# SoC_PS.net
KiCad netlist of a schematic drawn in Altium Designer
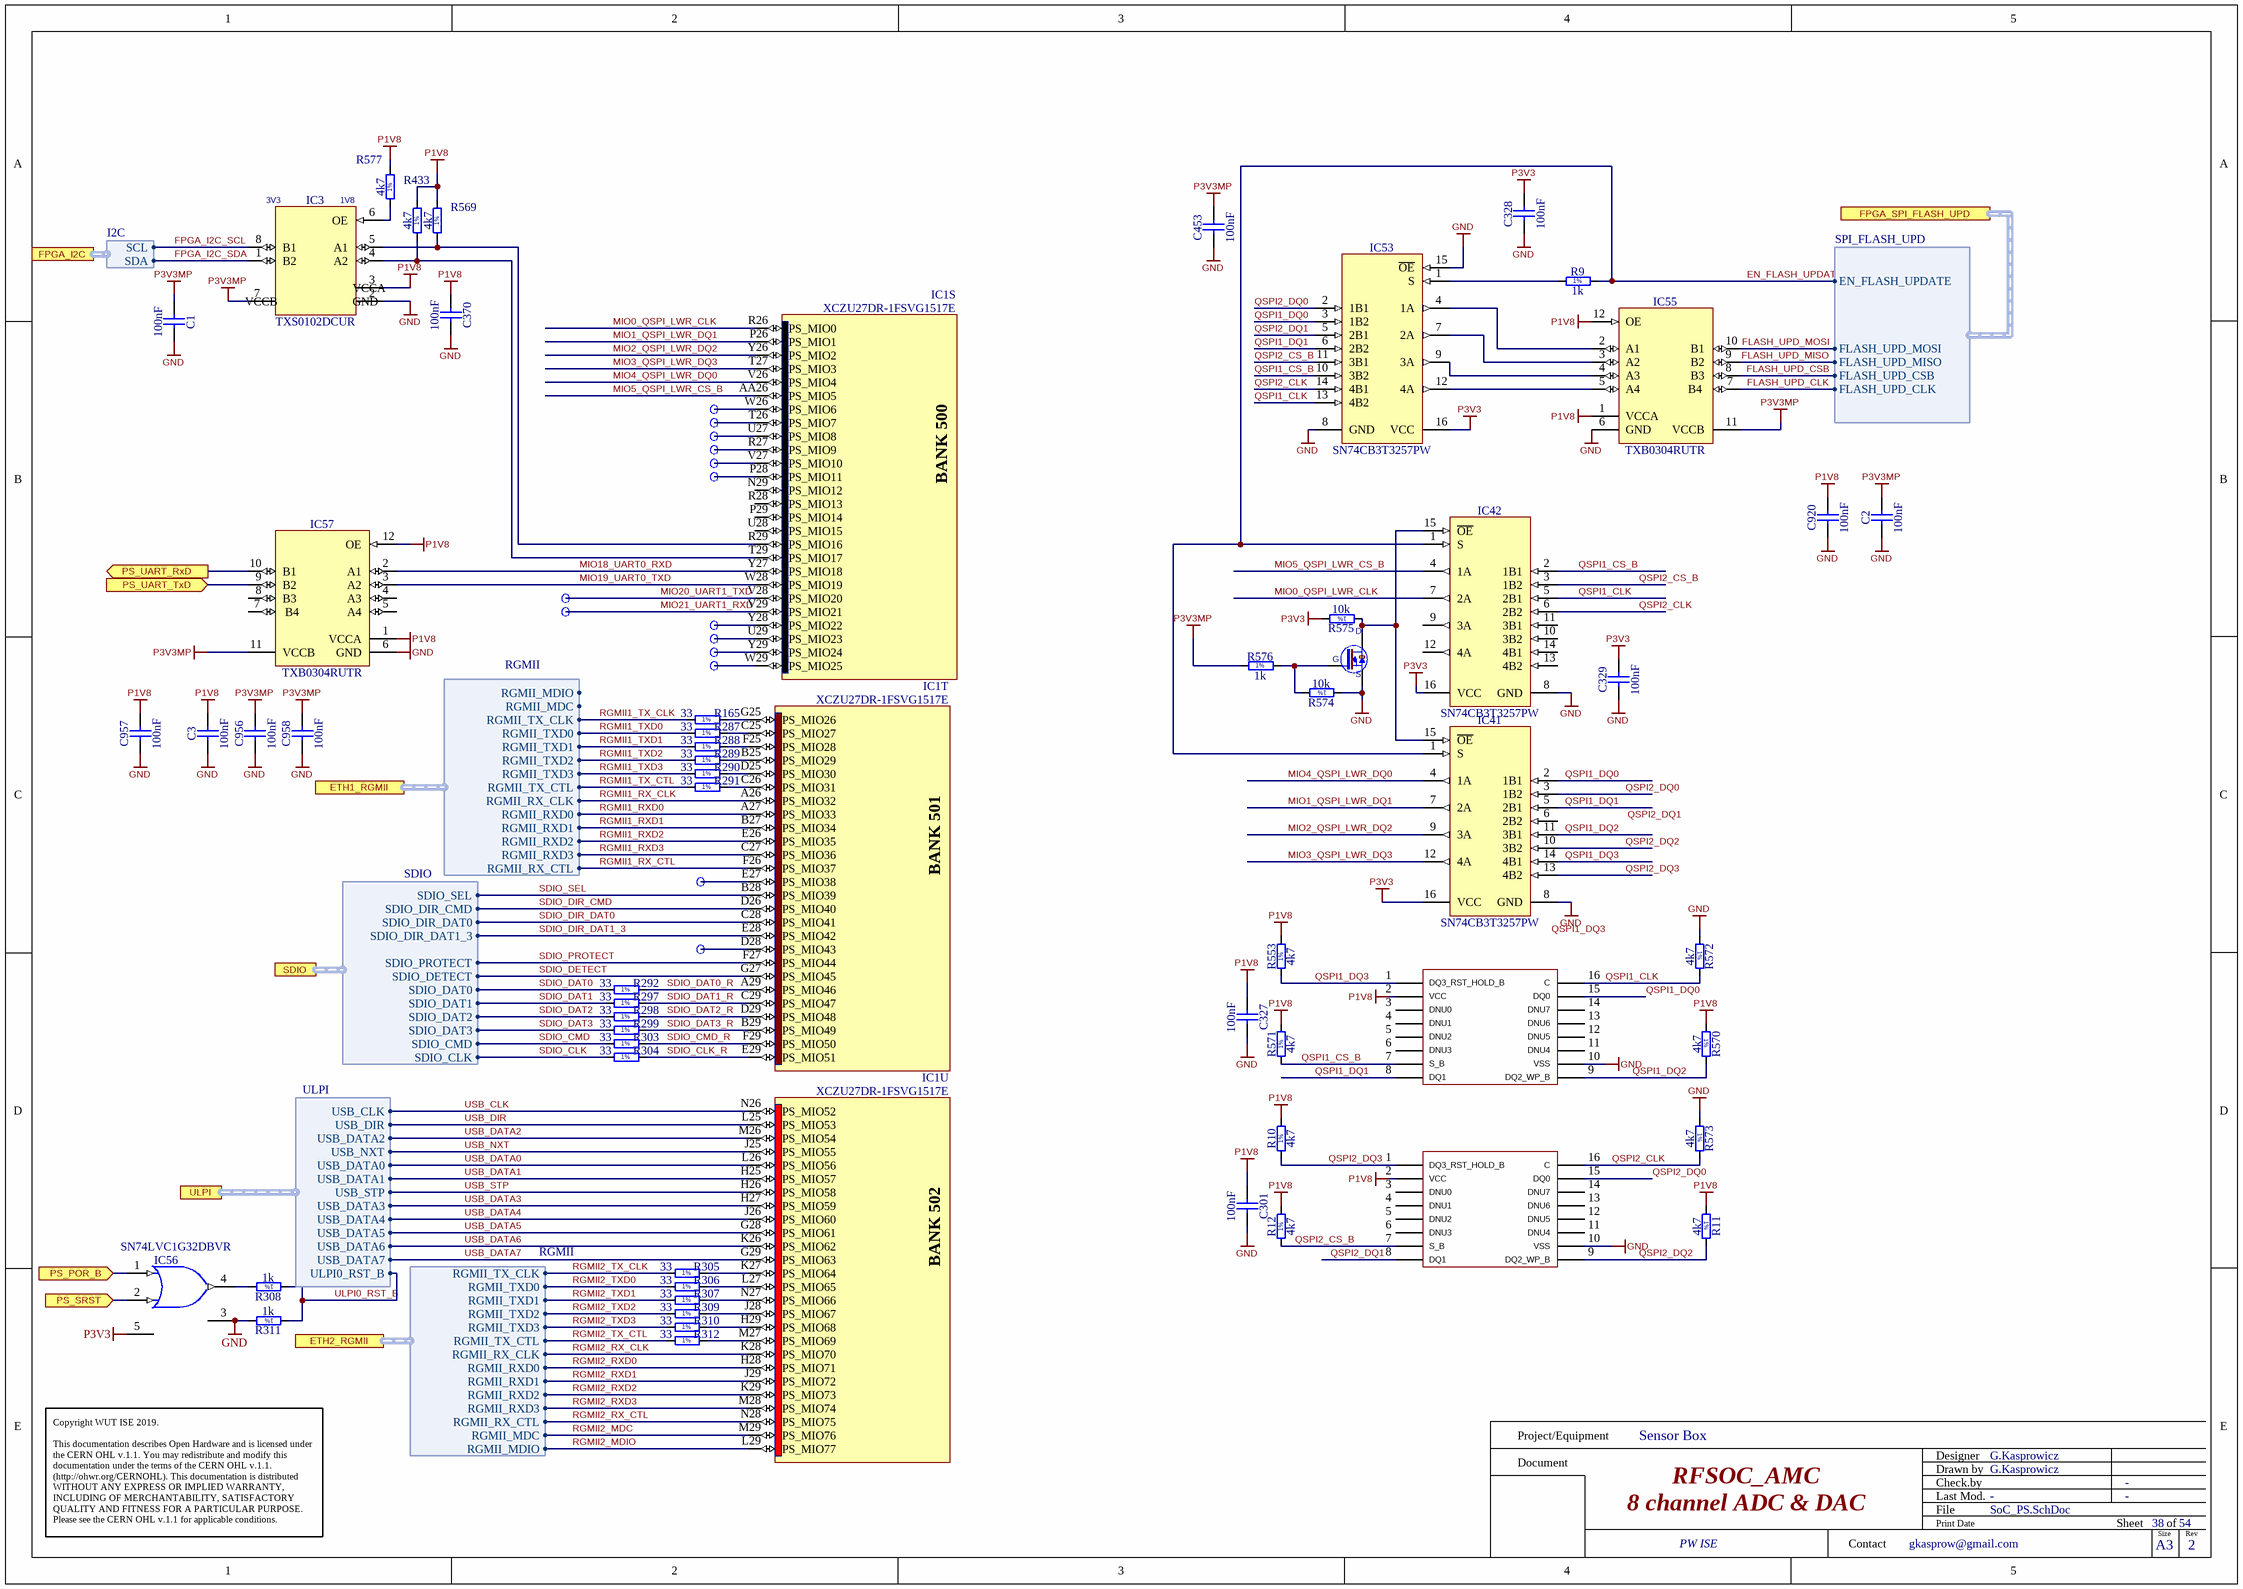
[diagram p0: SoC_PS.SchDoc]

(export (version "E")
  (design (tool "Eeschema 10.0.6"))
  (components
    (comp (ref "C1")
      (value "100nF")
      (footprint "CAPC0603X33N")
      (description "Non-polarised capacitor")
      (fields
        (field (name "MANUFACTURER PART NUMBER") "CC0201_100NF_6.3V_10%_X5R")
        (field (name "MANUFACTURER") "GENERIC")
        (field (name "AUTHOR") "CERN DEM JLC")
      )
      (libsource (lib "Capacitors") (part "Capacitor - non polarized"))
    )
    (comp (ref "C2")
      (value "100nF")
      (footprint "CAPC0603X33N")
      (description "Non-polarised capacitor")
      (fields
        (field (name "MANUFACTURER PART NUMBER") "CC0201_100NF_6.3V_10%_X5R")
        (field (name "MANUFACTURER") "GENERIC")
        (field (name "AUTHOR") "CERN DEM JLC")
      )
      (libsource (lib "Capacitors") (part "Capacitor - non polarized"))
    )
    (comp (ref "C3")
      (value "100nF")
      (footprint "CAPC0603X33N")
      (description "Non-polarised capacitor")
      (fields
        (field (name "MANUFACTURER PART NUMBER") "CC0201_100NF_6.3V_10%_X5R")
        (field (name "MANUFACTURER") "GENERIC")
        (field (name "AUTHOR") "CERN DEM JLC")
      )
      (libsource (lib "Capacitors") (part "Capacitor - non polarized"))
    )
    (comp (ref "C301")
      (value "100nF")
      (footprint "CAPC0603X33N")
      (description "Non-polarised capacitor")
      (fields
        (field (name "MANUFACTURER PART NUMBER") "CC0201_100NF_6.3V_10%_X5R")
        (field (name "MANUFACTURER") "GENERIC")
        (field (name "AUTHOR") "CERN DEM JLC")
      )
      (libsource (lib "Capacitors") (part "Capacitor - non polarized"))
    )
    (comp (ref "C327")
      (value "100nF")
      (footprint "CAPC0603X33N")
      (description "Non-polarised capacitor")
      (fields
        (field (name "MANUFACTURER PART NUMBER") "CC0201_100NF_6.3V_10%_X5R")
        (field (name "MANUFACTURER") "GENERIC")
        (field (name "AUTHOR") "CERN DEM JLC")
      )
      (libsource (lib "Capacitors") (part "Capacitor - non polarized"))
    )
    (comp (ref "C328")
      (value "100nF")
      (footprint "CAPC0603X33N")
      (description "Non-polarised capacitor")
      (fields
        (field (name "MANUFACTURER PART NUMBER") "CC0201_100NF_6.3V_10%_X5R")
        (field (name "MANUFACTURER") "GENERIC")
        (field (name "AUTHOR") "CERN DEM JLC")
      )
      (libsource (lib "Capacitors") (part "Capacitor - non polarized"))
    )
    (comp (ref "C329")
      (value "100nF")
      (footprint "CAPC0603X33N")
      (description "Non-polarised capacitor")
      (fields
        (field (name "MANUFACTURER PART NUMBER") "CC0201_100NF_6.3V_10%_X5R")
        (field (name "MANUFACTURER") "GENERIC")
        (field (name "AUTHOR") "CERN DEM JLC")
      )
      (libsource (lib "Capacitors") (part "Capacitor - non polarized"))
    )
    (comp (ref "C370")
      (value "100nF")
      (footprint "CAPC0603X33N")
      (description "Non-polarised capacitor")
      (fields
        (field (name "MANUFACTURER PART NUMBER") "CC0201_100NF_6.3V_10%_X5R")
        (field (name "MANUFACTURER") "GENERIC")
        (field (name "AUTHOR") "CERN DEM JLC")
      )
      (libsource (lib "Capacitors") (part "Capacitor - non polarized"))
    )
    (comp (ref "C453")
      (value "100nF")
      (footprint "CAPC0603X33N")
      (description "Non-polarised capacitor")
      (fields
        (field (name "MANUFACTURER PART NUMBER") "CC0201_100NF_6.3V_10%_X5R")
        (field (name "MANUFACTURER") "GENERIC")
        (field (name "AUTHOR") "CERN DEM JLC")
      )
      (libsource (lib "Capacitors") (part "Capacitor - non polarized"))
    )
    (comp (ref "C920")
      (value "100nF")
      (footprint "CAPC0603X33N")
      (description "Non-polarised capacitor")
      (fields
        (field (name "MANUFACTURER PART NUMBER") "CC0201_100NF_6.3V_10%_X5R")
        (field (name "MANUFACTURER") "GENERIC")
        (field (name "AUTHOR") "CERN DEM JLC")
      )
      (libsource (lib "Capacitors") (part "Capacitor - non polarized"))
    )
    (comp (ref "C956")
      (value "100nF")
      (footprint "CAPC0603X33N")
      (description "Non-polarised capacitor")
      (fields
        (field (name "MANUFACTURER PART NUMBER") "CC0201_100NF_6.3V_10%_X5R")
        (field (name "MANUFACTURER") "GENERIC")
        (field (name "AUTHOR") "CERN DEM JLC")
      )
      (libsource (lib "Capacitors") (part "Capacitor - non polarized"))
    )
    (comp (ref "C957")
      (value "100nF")
      (footprint "CAPC0603X33N")
      (description "Non-polarised capacitor")
      (fields
        (field (name "MANUFACTURER PART NUMBER") "CC0201_100NF_6.3V_10%_X5R")
        (field (name "MANUFACTURER") "GENERIC")
        (field (name "AUTHOR") "CERN DEM JLC")
      )
      (libsource (lib "Capacitors") (part "Capacitor - non polarized"))
    )
    (comp (ref "C958")
      (value "100nF")
      (footprint "CAPC0603X33N")
      (description "Non-polarised capacitor")
      (fields
        (field (name "MANUFACTURER PART NUMBER") "CC0201_100NF_6.3V_10%_X5R")
        (field (name "MANUFACTURER") "GENERIC")
        (field (name "AUTHOR") "CERN DEM JLC")
      )
      (libsource (lib "Capacitors") (part "Capacitor - non polarized"))
    )
    (comp (ref "IC1")
      (value "XCZU27DR-1FSVG1517E")
      (footprint "XILINX_FSVG1517 (XCZU27DR)")
      (fields (field (name "MANUFACTURER") "XILINX") (field (name "AUTHOR") "CERN DEM MR"))
      (libsource (lib "ICs And Semiconductors") (part "XCZU27DR-1FSVG1517E"))
    )
    (comp (ref "IC3")
      (value "TXS0102DCUR")
      (footprint "SOP50P310X90-8N")
      (description "2-Bit Bidirectionnal Voltage-Level Translator for Open-Drain And Push-Pull Applications")
      (fields (field (name "MANUFACTURER") "TEXAS INSTRUMENTS") (field (name "AUTHOR") "CERN DEM JLC"))
      (libsource (lib "ICs And Semiconductors") (part "TXS0102DCU"))
    )
    (comp (ref "IC37")
      (value "MT25QU512ABB8ESF")
      (footprint "SOIC127P1032X265-16N")
      (fields
        (field (name "MANUFACTURER PART NUMBER") "MT25QU512ABB8ESF-0SIT")
        (field (name "MANUFACTURER") "Micron")
      )
      (libsource (lib "") (part "root_0__*_1"))
    )
    (comp (ref "IC40")
      (value "MT25QU512ABB8ESF")
      (footprint "SOIC127P1032X265-16N")
      (fields
        (field (name "MANUFACTURER PART NUMBER") "MT25QU512ABB8ESF-0SIT")
        (field (name "MANUFACTURER") "Micron")
      )
      (libsource (lib "") (part "root_0__*_1"))
    )
    (comp (ref "IC41")
      (value "SN74CB3T3257PW")
      (footprint "SOP65P640X120-16N")
      (description "4-BIT 1-OF-2 FET Multiplexer/Demultiplexer 2.5V/3.3V Low-Voltage Bus Switch 5V Tolerant Shifter")
      (fields (field (name "MANUFACTURER") "TEXAS INSTRUMENTS") (field (name "AUTHOR") "CERN DEM JLC"))
      (libsource (lib "ICs And Semiconductors") (part "743257"))
    )
    (comp (ref "IC42")
      (value "SN74CB3T3257PW")
      (footprint "SOP65P640X120-16N")
      (description "4-BIT 1-OF-2 FET Multiplexer/Demultiplexer 2.5V/3.3V Low-Voltage Bus Switch 5V Tolerant Shifter")
      (fields (field (name "MANUFACTURER") "TEXAS INSTRUMENTS") (field (name "AUTHOR") "CERN DEM JLC"))
      (libsource (lib "ICs And Semiconductors") (part "743257"))
    )
    (comp (ref "IC53")
      (value "SN74CB3T3257PW")
      (footprint "SOP65P640X120-16N")
      (description "4-BIT 1-OF-2 FET Multiplexer/Demultiplexer 2.5V/3.3V Low-Voltage Bus Switch 5V Tolerant Shifter")
      (fields (field (name "MANUFACTURER") "TEXAS INSTRUMENTS") (field (name "AUTHOR") "CERN DEM JLC"))
      (libsource (lib "") (part "743257_1"))
    )
    (comp (ref "IC55")
      (value "TXB0304RUTR")
      (footprint "TEXAS_RUT (R-PUQFN-N12)")
      (description "4-bit Bidirectional Auto-direction Sensing Translator with Fully Symmetric 0.9V to 3.6V Range")
      (fields (field (name "MANUFACTURER") "TEXAS INSTRUMENTS") (field (name "AUTHOR") "CERN DEM JLC"))
      (libsource (lib "") (part "TXB0304RUTR_1"))
    )
    (comp (ref "IC56")
      (value "SN74LVC1G32DBVR")
      (footprint "SOT95P280X145-5N")
      (description "Single 2-Input Positive-OR Gate")
      (fields (field (name "MANUFACTURER") "TEXAS INSTRUMENTS") (field (name "AUTHOR") "CERN DEM JLC"))
      (libsource (lib "ICs And Semiconductors") (part "741G32"))
    )
    (comp (ref "IC57")
      (value "TXB0304RUTR")
      (footprint "TEXAS_RUT (R-PUQFN-N12)")
      (description "4-bit Bidirectional Auto-direction Sensing Translator with Fully Symmetric 0.9V to 3.6V Range")
      (fields (field (name "MANUFACTURER") "TEXAS INSTRUMENTS") (field (name "AUTHOR") "CERN DEM JLC"))
      (libsource (lib "ICs And Semiconductors") (part "TXB0304RUTR"))
    )
    (comp (ref "R9")
      (value "1k")
      (footprint "RESC1005X40N")
      (description "Resistor - 1%")
      (fields
        (field (name "MANUFACTURER PART NUMBER") "R0402_1K_1%_0.0625W_100PPM")
        (field (name "MANUFACTURER") "GENERIC")
        (field (name "AUTHOR") "CERN DEM JLC")
      )
      (libsource (lib "Resistors") (part "Resistor - 1%"))
    )
    (comp (ref "R10")
      (value "4k7")
      (footprint "RESC1005X40N")
      (description "Resistor - 1%")
      (fields
        (field (name "MANUFACTURER PART NUMBER") "R0402_4K7_1%_0.0625W_100PPM")
        (field (name "MANUFACTURER") "GENERIC")
        (field (name "AUTHOR") "CERN DEM JLC")
      )
      (libsource (lib "Resistors") (part "Resistor - 1%"))
    )
    (comp (ref "R11")
      (value "4k7")
      (footprint "RESC1005X40N")
      (description "Resistor - 1%")
      (fields
        (field (name "MANUFACTURER PART NUMBER") "R0402_4K7_1%_0.0625W_100PPM")
        (field (name "MANUFACTURER") "GENERIC")
        (field (name "AUTHOR") "CERN DEM JLC")
      )
      (libsource (lib "Resistors") (part "Resistor - 1%"))
    )
    (comp (ref "R12")
      (value "4k7")
      (footprint "RESC1005X40N")
      (description "Resistor - 1%")
      (fields
        (field (name "MANUFACTURER PART NUMBER") "R0402_4K7_1%_0.0625W_100PPM")
        (field (name "MANUFACTURER") "GENERIC")
        (field (name "AUTHOR") "CERN DEM JLC")
      )
      (libsource (lib "Resistors") (part "Resistor - 1%"))
    )
    (comp (ref "R165")
      (value "33")
      (footprint "RESC1005X40N")
      (description "Resistor - 1%")
      (fields
        (field (name "PART NUMBER") "R0402_33R_1%_0.0625W_100PPM")
        (field (name "POWER") "0.0625W")
        (field (name "AUTHOR") "CERN DEM JLC")
      )
      (libsource (lib "Resistors") (part "Resistor - 1%"))
    )
    (comp (ref "R287")
      (value "33")
      (footprint "RESC1005X40N")
      (description "Resistor - 1%")
      (fields
        (field (name "PART NUMBER") "R0402_33R_1%_0.0625W_100PPM")
        (field (name "POWER") "0.0625W")
        (field (name "AUTHOR") "CERN DEM JLC")
      )
      (libsource (lib "Resistors") (part "Resistor - 1%"))
    )
    (comp (ref "R288")
      (value "33")
      (footprint "RESC1005X40N")
      (description "Resistor - 1%")
      (fields
        (field (name "PART NUMBER") "R0402_33R_1%_0.0625W_100PPM")
        (field (name "POWER") "0.0625W")
        (field (name "AUTHOR") "CERN DEM JLC")
      )
      (libsource (lib "Resistors") (part "Resistor - 1%"))
    )
    (comp (ref "R289")
      (value "33")
      (footprint "RESC1005X40N")
      (description "Resistor - 1%")
      (fields
        (field (name "PART NUMBER") "R0402_33R_1%_0.0625W_100PPM")
        (field (name "POWER") "0.0625W")
        (field (name "AUTHOR") "CERN DEM JLC")
      )
      (libsource (lib "Resistors") (part "Resistor - 1%"))
    )
    (comp (ref "R290")
      (value "33")
      (footprint "RESC1005X40N")
      (description "Resistor - 1%")
      (fields
        (field (name "PART NUMBER") "R0402_33R_1%_0.0625W_100PPM")
        (field (name "POWER") "0.0625W")
        (field (name "AUTHOR") "CERN DEM JLC")
      )
      (libsource (lib "Resistors") (part "Resistor - 1%"))
    )
    (comp (ref "R291")
      (value "33")
      (footprint "RESC1005X40N")
      (description "Resistor - 1%")
      (fields
        (field (name "PART NUMBER") "R0402_33R_1%_0.0625W_100PPM")
        (field (name "POWER") "0.0625W")
        (field (name "AUTHOR") "CERN DEM JLC")
      )
      (libsource (lib "Resistors") (part "Resistor - 1%"))
    )
    (comp (ref "R292")
      (value "33")
      (footprint "RESC1005X40N")
      (description "Resistor - 1%")
      (fields
        (field (name "PART NUMBER") "R0402_33R_1%_0.0625W_100PPM")
        (field (name "POWER") "0.0625W")
        (field (name "AUTHOR") "CERN DEM JLC")
      )
      (libsource (lib "Resistors") (part "Resistor - 1%"))
    )
    (comp (ref "R297")
      (value "33")
      (footprint "RESC1005X40N")
      (description "Resistor - 1%")
      (fields
        (field (name "PART NUMBER") "R0402_33R_1%_0.0625W_100PPM")
        (field (name "POWER") "0.0625W")
        (field (name "AUTHOR") "CERN DEM JLC")
      )
      (libsource (lib "Resistors") (part "Resistor - 1%"))
    )
    (comp (ref "R298")
      (value "33")
      (footprint "RESC1005X40N")
      (description "Resistor - 1%")
      (fields
        (field (name "PART NUMBER") "R0402_33R_1%_0.0625W_100PPM")
        (field (name "POWER") "0.0625W")
        (field (name "AUTHOR") "CERN DEM JLC")
      )
      (libsource (lib "Resistors") (part "Resistor - 1%"))
    )
    (comp (ref "R299")
      (value "33")
      (footprint "RESC1005X40N")
      (description "Resistor - 1%")
      (fields
        (field (name "PART NUMBER") "R0402_33R_1%_0.0625W_100PPM")
        (field (name "POWER") "0.0625W")
        (field (name "AUTHOR") "CERN DEM JLC")
      )
      (libsource (lib "Resistors") (part "Resistor - 1%"))
    )
    (comp (ref "R303")
      (value "33")
      (footprint "RESC1005X40N")
      (description "Resistor - 1%")
      (fields
        (field (name "PART NUMBER") "R0402_33R_1%_0.0625W_100PPM")
        (field (name "POWER") "0.0625W")
        (field (name "AUTHOR") "CERN DEM JLC")
      )
      (libsource (lib "Resistors") (part "Resistor - 1%"))
    )
    (comp (ref "R304")
      (value "33")
      (footprint "RESC1005X40N")
      (description "Resistor - 1%")
      (fields
        (field (name "PART NUMBER") "R0402_33R_1%_0.0625W_100PPM")
        (field (name "POWER") "0.0625W")
        (field (name "AUTHOR") "CERN DEM JLC")
      )
      (libsource (lib "Resistors") (part "Resistor - 1%"))
    )
    (comp (ref "R305")
      (value "33")
      (footprint "RESC1005X40N")
      (description "Resistor - 1%")
      (fields
        (field (name "PART NUMBER") "R0402_33R_1%_0.0625W_100PPM")
        (field (name "POWER") "0.0625W")
        (field (name "AUTHOR") "CERN DEM JLC")
      )
      (libsource (lib "Resistors") (part "Resistor - 1%"))
    )
    (comp (ref "R306")
      (value "33")
      (footprint "RESC1005X40N")
      (description "Resistor - 1%")
      (fields
        (field (name "PART NUMBER") "R0402_33R_1%_0.0625W_100PPM")
        (field (name "POWER") "0.0625W")
        (field (name "AUTHOR") "CERN DEM JLC")
      )
      (libsource (lib "Resistors") (part "Resistor - 1%"))
    )
    (comp (ref "R307")
      (value "33")
      (footprint "RESC1005X40N")
      (description "Resistor - 1%")
      (fields
        (field (name "PART NUMBER") "R0402_33R_1%_0.0625W_100PPM")
        (field (name "POWER") "0.0625W")
        (field (name "AUTHOR") "CERN DEM JLC")
      )
      (libsource (lib "Resistors") (part "Resistor - 1%"))
    )
    (comp (ref "R308")
      (value "1k")
      (footprint "RESC1005X40N")
      (description "Resistor - 1%")
      (fields
        (field (name "PART NUMBER") "R0402_1K_1%_0.0625W_100PPM")
        (field (name "POWER") "0.0625W")
        (field (name "AUTHOR") "CERN DEM JLC")
      )
      (libsource (lib "Resistors") (part "Resistor - 1%"))
    )
    (comp (ref "R309")
      (value "33")
      (footprint "RESC1005X40N")
      (description "Resistor - 1%")
      (fields
        (field (name "PART NUMBER") "R0402_33R_1%_0.0625W_100PPM")
        (field (name "POWER") "0.0625W")
        (field (name "AUTHOR") "CERN DEM JLC")
      )
      (libsource (lib "Resistors") (part "Resistor - 1%"))
    )
    (comp (ref "R310")
      (value "33")
      (footprint "RESC1005X40N")
      (description "Resistor - 1%")
      (fields
        (field (name "PART NUMBER") "R0402_33R_1%_0.0625W_100PPM")
        (field (name "POWER") "0.0625W")
        (field (name "AUTHOR") "CERN DEM JLC")
      )
      (libsource (lib "Resistors") (part "Resistor - 1%"))
    )
    (comp (ref "R311")
      (value "1k")
      (footprint "RESC1005X40N")
      (description "Resistor - 1%")
      (fields
        (field (name "PART NUMBER") "R0402_1K_1%_0.0625W_100PPM")
        (field (name "POWER") "0.0625W")
        (field (name "AUTHOR") "CERN DEM JLC")
      )
      (libsource (lib "Resistors") (part "Resistor - 1%"))
    )
    (comp (ref "R312")
      (value "33")
      (footprint "RESC1005X40N")
      (description "Resistor - 1%")
      (fields
        (field (name "PART NUMBER") "R0402_33R_1%_0.0625W_100PPM")
        (field (name "POWER") "0.0625W")
        (field (name "AUTHOR") "CERN DEM JLC")
      )
      (libsource (lib "Resistors") (part "Resistor - 1%"))
    )
    (comp (ref "R433")
      (value "4k7")
      (footprint "RESC1005X40N")
      (description "Resistor - 1%")
      (fields
        (field (name "MANUFACTURER PART NUMBER") "R0402_4K7_1%_0.0625W_100PPM")
        (field (name "MANUFACTURER") "GENERIC")
        (field (name "AUTHOR") "CERN DEM JLC")
      )
      (libsource (lib "Resistors") (part "Resistor - 1%"))
    )
    (comp (ref "R553")
      (value "4k7")
      (footprint "RESC1005X40N")
      (description "Resistor - 1%")
      (fields
        (field (name "MANUFACTURER PART NUMBER") "R0402_4K7_1%_0.0625W_100PPM")
        (field (name "MANUFACTURER") "GENERIC")
        (field (name "AUTHOR") "CERN DEM JLC")
      )
      (libsource (lib "Resistors") (part "Resistor - 1%"))
    )
    (comp (ref "R569")
      (value "4k7")
      (footprint "RESC1005X40N")
      (description "Resistor - 1%")
      (fields
        (field (name "MANUFACTURER PART NUMBER") "R0402_4K7_1%_0.0625W_100PPM")
        (field (name "MANUFACTURER") "GENERIC")
        (field (name "AUTHOR") "CERN DEM JLC")
      )
      (libsource (lib "Resistors") (part "Resistor - 1%"))
    )
    (comp (ref "R570")
      (value "4k7")
      (footprint "RESC1005X40N")
      (description "Resistor - 1%")
      (fields
        (field (name "MANUFACTURER PART NUMBER") "R0402_4K7_1%_0.0625W_100PPM")
        (field (name "MANUFACTURER") "GENERIC")
        (field (name "AUTHOR") "CERN DEM JLC")
      )
      (libsource (lib "Resistors") (part "Resistor - 1%"))
    )
    (comp (ref "R571")
      (value "4k7")
      (footprint "RESC1005X40N")
      (description "Resistor - 1%")
      (fields
        (field (name "MANUFACTURER PART NUMBER") "R0402_4K7_1%_0.0625W_100PPM")
        (field (name "MANUFACTURER") "GENERIC")
        (field (name "AUTHOR") "CERN DEM JLC")
      )
      (libsource (lib "Resistors") (part "Resistor - 1%"))
    )
    (comp (ref "R572")
      (value "4k7")
      (footprint "RESC1005X40N")
      (description "Resistor - 1%")
      (fields
        (field (name "MANUFACTURER PART NUMBER") "R0402_4K7_1%_0.0625W_100PPM")
        (field (name "MANUFACTURER") "GENERIC")
        (field (name "AUTHOR") "CERN DEM JLC")
      )
      (libsource (lib "Resistors") (part "Resistor - 1%"))
    )
    (comp (ref "R573")
      (value "4k7")
      (footprint "RESC1005X40N")
      (description "Resistor - 1%")
      (fields
        (field (name "MANUFACTURER PART NUMBER") "R0402_4K7_1%_0.0625W_100PPM")
        (field (name "MANUFACTURER") "GENERIC")
        (field (name "AUTHOR") "CERN DEM JLC")
      )
      (libsource (lib "Resistors") (part "Resistor - 1%"))
    )
    (comp (ref "R574")
      (value "10k")
      (footprint "RESC1005X40N")
      (description "Resistor - 1%")
      (fields
        (field (name "MANUFACTURER PART NUMBER") "R0402_10K_1%_0.0625W_100PPM")
        (field (name "MANUFACTURER") "GENERIC")
        (field (name "AUTHOR") "CERN DEM JLC")
      )
      (libsource (lib "Resistors") (part "Resistor - 1%"))
    )
    (comp (ref "R575")
      (value "10k")
      (footprint "RESC1005X40N")
      (description "Resistor - 1%")
      (fields
        (field (name "MANUFACTURER PART NUMBER") "R0402_10K_1%_0.0625W_100PPM")
        (field (name "MANUFACTURER") "GENERIC")
        (field (name "AUTHOR") "CERN DEM JLC")
      )
      (libsource (lib "Resistors") (part "Resistor - 1%"))
    )
    (comp (ref "R576")
      (value "1k")
      (footprint "RESC1005X40N")
      (description "Resistor - 1%")
      (fields
        (field (name "MANUFACTURER PART NUMBER") "R0402_1K_1%_0.0625W_100PPM")
        (field (name "MANUFACTURER") "GENERIC")
        (field (name "AUTHOR") "CERN DEM JLC")
      )
      (libsource (lib "Resistors") (part "Resistor - 1%"))
    )
    (comp (ref "R577")
      (value "4k7")
      (footprint "RESC1005X40N")
      (description "Resistor - 1%")
      (fields
        (field (name "MANUFACTURER PART NUMBER") "R0402_4K7_1%_0.0625W_100PPM")
        (field (name "MANUFACTURER") "GENERIC")
        (field (name "AUTHOR") "CERN DEM JLC")
      )
      (libsource (lib "Resistors") (part "Resistor - 1%"))
    )
    (comp (ref "T22")
      (value "BSS138LT1G")
      (fields (field (name "MANUFACTURER") "ON SEMICONDUCTOR"))
      (libsource (lib "") (part "root_0__*_2"))
    )
    (comp (ref "TP11") (value "SMD_PAD_D1MM") (libsource (lib "altium-import") (part "root_0__*")))
    (comp (ref "TP12") (value "SMD_PAD_D1MM") (libsource (lib "altium-import") (part "root_0__*")))
    (comp (ref "TP13") (value "SMD_PAD_D1MM") (libsource (lib "altium-import") (part "root_0__*")))
    (comp (ref "TP14") (value "SMD_PAD_D1MM") (libsource (lib "altium-import") (part "root_0__*")))
    (comp (ref "TP15") (value "SMD_PAD_D1MM") (libsource (lib "altium-import") (part "root_0__*")))
    (comp (ref "TP16") (value "SMD_PAD_D1MM") (libsource (lib "altium-import") (part "root_0__*")))
    (comp (ref "TP17") (value "SMD_PAD_D1MM") (libsource (lib "altium-import") (part "root_0__*")))
    (comp (ref "TP18") (value "SMD_PAD_D1MM") (libsource (lib "altium-import") (part "root_0__*")))
    (comp (ref "TP19") (value "SMD_PAD_D1MM") (libsource (lib "altium-import") (part "root_0__*")))
    (comp (ref "TP20") (value "SMD_PAD_D1MM") (libsource (lib "altium-import") (part "root_0__*")))
    (comp (ref "TP21") (value "SMD_PAD_D1MM") (libsource (lib "altium-import") (part "root_0__*")))
    (comp (ref "TP22") (value "SMD_PAD_D1MM") (libsource (lib "altium-import") (part "root_0__*")))
    (comp (ref "TP23") (value "SMD_PAD_D1MM") (libsource (lib "altium-import") (part "root_0__*")))
    (comp (ref "TP24") (value "SMD_PAD_D1MM") (libsource (lib "altium-import") (part "root_0__*")))
  )
  (nets
    (net (code "6") (name "/EN_FLASH_UPDATE") (class "Default")
      (node (ref "IC41") (pin "1") (pinfunction "S_1") (pintype "input"))
      (node (ref "IC42") (pin "1") (pinfunction "S_1") (pintype "input"))
      (node (ref "R9") (pin "2") (pinfunction "2_2") (pintype "passive"))
    )
    (net (code "7") (name "/FLASH_UPD_CLK") (class "Default")
      (node (ref "IC55") (pin "7") (pinfunction "B4_7") (pintype "bidirectional"))
    )
    (net (code "8") (name "/FLASH_UPD_CSB") (class "Default")
      (node (ref "IC55") (pin "8") (pinfunction "B3_8") (pintype "bidirectional"))
    )
    (net (code "9") (name "/FLASH_UPD_MISO") (class "Default")
      (node (ref "IC55") (pin "9") (pinfunction "B2_9") (pintype "bidirectional"))
    )
    (net (code "10") (name "/FLASH_UPD_MOSI") (class "Default")
      (node (ref "IC55") (pin "10") (pinfunction "B1_10") (pintype "bidirectional"))
    )
    (net (code "11") (name "/FPGA_I2C_SCL") (class "Default")
      (node (ref "IC3") (pin "8") (pinfunction "B1_8") (pintype "bidirectional"))
    )
    (net (code "12") (name "/FPGA_I2C_SDA") (class "Default")
      (node (ref "IC3") (pin "1") (pinfunction "B2_1") (pintype "bidirectional"))
    )
    (net (code "13") (name "/MIO0_QSPI_LWR_CLK") (class "Default")
      (node (ref "IC1") (pin "R26") (pinfunction "PS_MIO0_R26") (pintype "bidirectional"))
      (node (ref "IC42") (pin "7") (pinfunction "2A_7") (pintype "output"))
    )
    (net (code "14") (name "/MIO1_QSPI_LWR_DQ1") (class "Default")
      (node (ref "IC1") (pin "P26") (pinfunction "PS_MIO1_P26") (pintype "bidirectional"))
      (node (ref "IC41") (pin "7") (pinfunction "2A_7") (pintype "output"))
    )
    (net (code "15") (name "/MIO2_QSPI_LWR_DQ2") (class "Default")
      (node (ref "IC1") (pin "Y26") (pinfunction "PS_MIO2_Y26") (pintype "bidirectional"))
      (node (ref "IC41") (pin "9") (pinfunction "3A_9") (pintype "output"))
    )
    (net (code "16") (name "/MIO3_QSPI_LWR_DQ3") (class "Default")
      (node (ref "IC1") (pin "T27") (pinfunction "PS_MIO3_T27") (pintype "bidirectional"))
      (node (ref "IC41") (pin "12") (pinfunction "4A_12") (pintype "output"))
    )
    (net (code "17") (name "/MIO4_QSPI_LWR_DQ0") (class "Default")
      (node (ref "IC1") (pin "V26") (pinfunction "PS_MIO4_V26") (pintype "bidirectional"))
      (node (ref "IC41") (pin "4") (pinfunction "1A_4") (pintype "output"))
    )
    (net (code "18") (name "/MIO5_QSPI_LWR_CS_B") (class "Default")
      (node (ref "IC1") (pin "AA26") (pinfunction "PS_MIO5_AA26") (pintype "bidirectional"))
      (node (ref "IC42") (pin "4") (pinfunction "1A_4") (pintype "output"))
    )
    (net (code "19") (name "/MIO18_UART0_RXD") (class "Default")
      (node (ref "IC1") (pin "Y27") (pinfunction "PS_MIO18_Y27") (pintype "bidirectional"))
      (node (ref "IC57") (pin "2") (pinfunction "A1_2") (pintype "bidirectional"))
    )
    (net (code "20") (name "/MIO19_UART0_TXD") (class "Default")
      (node (ref "IC1") (pin "W28") (pinfunction "PS_MIO19_W28") (pintype "bidirectional"))
      (node (ref "IC57") (pin "3") (pinfunction "A2_3") (pintype "bidirectional"))
    )
    (net (code "21") (name "/MIO20_UART1_TXD") (class "Default")
      (node (ref "IC1") (pin "V28") (pinfunction "PS_MIO20_V28") (pintype "bidirectional"))
      (node (ref "TP22") (pin "1") (pinfunction "1_1") (pintype "passive"))
    )
    (net (code "22") (name "/MIO21_UART1_RXD") (class "Default")
      (node (ref "IC1") (pin "V29") (pinfunction "PS_MIO21_V29") (pintype "bidirectional"))
      (node (ref "TP23") (pin "1") (pinfunction "1_1") (pintype "passive"))
    )
    (net (code "23") (name "/PS_POR_B") (class "Default")
      (node (ref "IC56") (pin "1") (pinfunction "A_1") (pintype "input"))
    )
    (net (code "24") (name "/PS_SRST") (class "Default")
      (node (ref "IC56") (pin "2") (pinfunction "B_2") (pintype "input"))
    )
    (net (code "25") (name "/PS_UART_RxD") (class "Default")
      (node (ref "IC57") (pin "10") (pinfunction "B1_10") (pintype "bidirectional"))
    )
    (net (code "26") (name "/PS_UART_TxD") (class "Default")
      (node (ref "IC57") (pin "9") (pinfunction "B2_9") (pintype "bidirectional"))
    )
    (net (code "27") (name "/QSPI1_CLK") (class "Default")
      (node (ref "IC37") (pin "16") (pinfunction "C_16") (pintype "passive"))
      (node (ref "IC42") (pin "5") (pinfunction "2B1_5") (pintype "input"))
      (node (ref "IC53") (pin "13") (pinfunction "4B2_13") (pintype "input"))
      (node (ref "R572") (pin "2") (pinfunction "2_2") (pintype "passive"))
    )
    (net (code "28") (name "/QSPI1_CS_B") (class "Default")
      (node (ref "IC37") (pin "7") (pinfunction "S_B_7") (pintype "passive"))
      (node (ref "IC42") (pin "2") (pinfunction "1B1_2") (pintype "input"))
      (node (ref "IC53") (pin "10") (pinfunction "3B2_10") (pintype "input"))
      (node (ref "R571") (pin "1") (pinfunction "1_1") (pintype "passive"))
    )
    (net (code "29") (name "/QSPI1_DQ0") (class "Default")
      (node (ref "IC37") (pin "15") (pinfunction "DQ0_15") (pintype "passive"))
      (node (ref "IC41") (pin "2") (pinfunction "1B1_2") (pintype "input"))
      (node (ref "IC53") (pin "3") (pinfunction "1B2_3") (pintype "input"))
    )
    (net (code "30") (name "/QSPI1_DQ1") (class "Default")
      (node (ref "IC37") (pin "8") (pinfunction "DQ1_8") (pintype "passive"))
      (node (ref "IC41") (pin "5") (pinfunction "2B1_5") (pintype "input"))
      (node (ref "IC53") (pin "6") (pinfunction "2B2_6") (pintype "input"))
    )
    (net (code "31") (name "/QSPI1_DQ2") (class "Default")
      (node (ref "IC37") (pin "9") (pinfunction "DQ2_WP_B_9") (pintype "passive"))
      (node (ref "IC41") (pin "11") (pinfunction "3B1_11") (pintype "input"))
      (node (ref "R570") (pin "2") (pinfunction "2_2") (pintype "passive"))
    )
    (net (code "32") (name "/QSPI1_DQ3") (class "Default")
      (node (ref "IC37") (pin "1") (pinfunction "DQ3_RST_HOLD_B_1") (pintype "passive"))
      (node (ref "IC41") (pin "14") (pinfunction "4B1_14") (pintype "input"))
      (node (ref "R553") (pin "1") (pinfunction "1_1") (pintype "passive"))
    )
    (net (code "33") (name "/QSPI2_CLK") (class "Default")
      (node (ref "IC40") (pin "16") (pinfunction "C_16") (pintype "passive"))
      (node (ref "IC42") (pin "6") (pinfunction "2B2_6") (pintype "input"))
      (node (ref "IC53") (pin "14") (pinfunction "4B1_14") (pintype "input"))
      (node (ref "R573") (pin "2") (pinfunction "2_2") (pintype "passive"))
    )
    (net (code "34") (name "/QSPI2_CS_B") (class "Default")
      (node (ref "IC40") (pin "7") (pinfunction "S_B_7") (pintype "passive"))
      (node (ref "IC42") (pin "3") (pinfunction "1B2_3") (pintype "input"))
      (node (ref "IC53") (pin "11") (pinfunction "3B1_11") (pintype "input"))
      (node (ref "R12") (pin "1") (pinfunction "1_1") (pintype "passive"))
    )
    (net (code "35") (name "/QSPI2_DQ0") (class "Default")
      (node (ref "IC40") (pin "15") (pinfunction "DQ0_15") (pintype "passive"))
      (node (ref "IC41") (pin "3") (pinfunction "1B2_3") (pintype "input"))
      (node (ref "IC53") (pin "2") (pinfunction "1B1_2") (pintype "input"))
    )
    (net (code "36") (name "/QSPI2_DQ1") (class "Default")
      (node (ref "IC40") (pin "8") (pinfunction "DQ1_8") (pintype "passive"))
      (node (ref "IC53") (pin "5") (pinfunction "2B1_5") (pintype "input"))
    )
    (net (code "37") (name "/QSPI2_DQ2") (class "Default")
      (node (ref "IC40") (pin "9") (pinfunction "DQ2_WP_B_9") (pintype "passive"))
      (node (ref "IC41") (pin "10") (pinfunction "3B2_10") (pintype "input"))
      (node (ref "R11") (pin "2") (pinfunction "2_2") (pintype "passive"))
    )
    (net (code "38") (name "/QSPI2_DQ3") (class "Default")
      (node (ref "IC40") (pin "1") (pinfunction "DQ3_RST_HOLD_B_1") (pintype "passive"))
      (node (ref "IC41") (pin "13") (pinfunction "4B2_13") (pintype "input"))
      (node (ref "R10") (pin "1") (pinfunction "1_1") (pintype "passive"))
    )
    (net (code "39") (name "/RGMII1_RXD0") (class "Default")
      (node (ref "IC1") (pin "A27") (pinfunction "PS_MIO33_A27") (pintype "bidirectional"))
    )
    (net (code "40") (name "/RGMII1_RXD1") (class "Default")
      (node (ref "IC1") (pin "B27") (pinfunction "PS_MIO34_B27") (pintype "bidirectional"))
    )
    (net (code "41") (name "/RGMII1_RXD2") (class "Default")
      (node (ref "IC1") (pin "E26") (pinfunction "PS_MIO35_E26") (pintype "bidirectional"))
    )
    (net (code "42") (name "/RGMII1_RXD3") (class "Default")
      (node (ref "IC1") (pin "C27") (pinfunction "PS_MIO36_C27") (pintype "bidirectional"))
    )
    (net (code "43") (name "/RGMII1_RX_CLK") (class "Default")
      (node (ref "IC1") (pin "A26") (pinfunction "PS_MIO32_A26") (pintype "bidirectional"))
    )
    (net (code "44") (name "/RGMII1_RX_CTL") (class "Default")
      (node (ref "IC1") (pin "F26") (pinfunction "PS_MIO37_F26") (pintype "bidirectional"))
    )
    (net (code "45") (name "/RGMII1_TXD0") (class "Default")
      (node (ref "R287") (pin "1") (pinfunction "1_1") (pintype "passive"))
    )
    (net (code "46") (name "/RGMII1_TXD1") (class "Default")
      (node (ref "R288") (pin "1") (pinfunction "1_1") (pintype "passive"))
    )
    (net (code "47") (name "/RGMII1_TXD2") (class "Default")
      (node (ref "R289") (pin "1") (pinfunction "1_1") (pintype "passive"))
    )
    (net (code "48") (name "/RGMII1_TXD3") (class "Default")
      (node (ref "R290") (pin "1") (pinfunction "1_1") (pintype "passive"))
    )
    (net (code "49") (name "/RGMII1_TX_CLK") (class "Default")
      (node (ref "R165") (pin "1") (pinfunction "1_1") (pintype "passive"))
    )
    (net (code "50") (name "/RGMII1_TX_CTL") (class "Default")
      (node (ref "R291") (pin "1") (pinfunction "1_1") (pintype "passive"))
    )
    (net (code "51") (name "/RGMII2_MDC") (class "Default")
      (node (ref "IC1") (pin "M29") (pinfunction "PS_MIO76_M29") (pintype "bidirectional"))
    )
    (net (code "52") (name "/RGMII2_MDIO") (class "Default")
      (node (ref "IC1") (pin "L29") (pinfunction "PS_MIO77_L29") (pintype "bidirectional"))
    )
    (net (code "53") (name "/RGMII2_RXD0") (class "Default")
      (node (ref "IC1") (pin "H28") (pinfunction "PS_MIO71_H28") (pintype "bidirectional"))
    )
    (net (code "54") (name "/RGMII2_RXD1") (class "Default")
      (node (ref "IC1") (pin "J29") (pinfunction "PS_MIO72_J29") (pintype "bidirectional"))
    )
    (net (code "55") (name "/RGMII2_RXD2") (class "Default")
      (node (ref "IC1") (pin "K29") (pinfunction "PS_MIO73_K29") (pintype "bidirectional"))
    )
    (net (code "56") (name "/RGMII2_RXD3") (class "Default")
      (node (ref "IC1") (pin "M28") (pinfunction "PS_MIO74_M28") (pintype "bidirectional"))
    )
    (net (code "57") (name "/RGMII2_RX_CLK") (class "Default")
      (node (ref "IC1") (pin "K28") (pinfunction "PS_MIO70_K28") (pintype "bidirectional"))
    )
    (net (code "58") (name "/RGMII2_RX_CTL") (class "Default")
      (node (ref "IC1") (pin "N28") (pinfunction "PS_MIO75_N28") (pintype "bidirectional"))
    )
    (net (code "59") (name "/RGMII2_TXD0") (class "Default")
      (node (ref "R306") (pin "1") (pinfunction "1_1") (pintype "passive"))
    )
    (net (code "60") (name "/RGMII2_TXD1") (class "Default")
      (node (ref "R307") (pin "1") (pinfunction "1_1") (pintype "passive"))
    )
    (net (code "61") (name "/RGMII2_TXD2") (class "Default")
      (node (ref "R309") (pin "1") (pinfunction "1_1") (pintype "passive"))
    )
    (net (code "62") (name "/RGMII2_TXD3") (class "Default")
      (node (ref "R310") (pin "1") (pinfunction "1_1") (pintype "passive"))
    )
    (net (code "63") (name "/RGMII2_TX_CLK") (class "Default")
      (node (ref "R305") (pin "1") (pinfunction "1_1") (pintype "passive"))
    )
    (net (code "64") (name "/RGMII2_TX_CTL") (class "Default")
      (node (ref "R312") (pin "1") (pinfunction "1_1") (pintype "passive"))
    )
    (net (code "65") (name "/SDIO_CLK") (class "Default")
      (node (ref "R304") (pin "1") (pinfunction "1_1") (pintype "passive"))
    )
    (net (code "66") (name "/SDIO_CLK_R") (class "Default")
      (node (ref "IC1") (pin "E29") (pinfunction "PS_MIO51_E29") (pintype "bidirectional"))
      (node (ref "R304") (pin "2") (pinfunction "2_2") (pintype "passive"))
    )
    (net (code "67") (name "/SDIO_CMD") (class "Default")
      (node (ref "R303") (pin "1") (pinfunction "1_1") (pintype "passive"))
    )
    (net (code "68") (name "/SDIO_CMD_R") (class "Default")
      (node (ref "IC1") (pin "F29") (pinfunction "PS_MIO50_F29") (pintype "bidirectional"))
      (node (ref "R303") (pin "2") (pinfunction "2_2") (pintype "passive"))
    )
    (net (code "69") (name "/SDIO_DAT0") (class "Default")
      (node (ref "R292") (pin "1") (pinfunction "1_1") (pintype "passive"))
    )
    (net (code "70") (name "/SDIO_DAT0_R") (class "Default")
      (node (ref "IC1") (pin "A29") (pinfunction "PS_MIO46_A29") (pintype "bidirectional"))
      (node (ref "R292") (pin "2") (pinfunction "2_2") (pintype "passive"))
    )
    (net (code "71") (name "/SDIO_DAT1") (class "Default")
      (node (ref "R297") (pin "1") (pinfunction "1_1") (pintype "passive"))
    )
    (net (code "72") (name "/SDIO_DAT1_R") (class "Default")
      (node (ref "IC1") (pin "C29") (pinfunction "PS_MIO47_C29") (pintype "bidirectional"))
      (node (ref "R297") (pin "2") (pinfunction "2_2") (pintype "passive"))
    )
    (net (code "73") (name "/SDIO_DAT2") (class "Default")
      (node (ref "R298") (pin "1") (pinfunction "1_1") (pintype "passive"))
    )
    (net (code "74") (name "/SDIO_DAT2_R") (class "Default")
      (node (ref "IC1") (pin "D29") (pinfunction "PS_MIO48_D29") (pintype "bidirectional"))
      (node (ref "R298") (pin "2") (pinfunction "2_2") (pintype "passive"))
    )
    (net (code "75") (name "/SDIO_DAT3") (class "Default")
      (node (ref "R299") (pin "1") (pinfunction "1_1") (pintype "passive"))
    )
    (net (code "76") (name "/SDIO_DAT3_R") (class "Default")
      (node (ref "IC1") (pin "B29") (pinfunction "PS_MIO49_B29") (pintype "bidirectional"))
      (node (ref "R299") (pin "2") (pinfunction "2_2") (pintype "passive"))
    )
    (net (code "77") (name "/SDIO_DETECT") (class "Default")
      (node (ref "IC1") (pin "G27") (pinfunction "PS_MIO45_G27") (pintype "bidirectional"))
    )
    (net (code "78") (name "/SDIO_DIR_CMD") (class "Default")
      (node (ref "IC1") (pin "D26") (pinfunction "PS_MIO40_D26") (pintype "bidirectional"))
    )
    (net (code "79") (name "/SDIO_DIR_DAT0") (class "Default")
      (node (ref "IC1") (pin "C28") (pinfunction "PS_MIO41_C28") (pintype "bidirectional"))
    )
    (net (code "80") (name "/SDIO_DIR_DAT1_3") (class "Default")
      (node (ref "IC1") (pin "E28") (pinfunction "PS_MIO42_E28") (pintype "bidirectional"))
    )
    (net (code "81") (name "/SDIO_PROTECT") (class "Default")
      (node (ref "IC1") (pin "F27") (pinfunction "PS_MIO44_F27") (pintype "bidirectional"))
    )
    (net (code "82") (name "/SDIO_SEL") (class "Default")
      (node (ref "IC1") (pin "B28") (pinfunction "PS_MIO39_B28") (pintype "bidirectional"))
    )
    (net (code "83") (name "/ULPI0_RST_B") (class "Default")
      (node (ref "R308") (pin "1") (pinfunction "1_1") (pintype "passive"))
      (node (ref "R311") (pin "1") (pinfunction "1_1") (pintype "passive"))
    )
    (net (code "84") (name "/USB_CLK") (class "Default")
      (node (ref "IC1") (pin "N26") (pinfunction "PS_MIO52_N26") (pintype "bidirectional"))
    )
    (net (code "85") (name "/USB_DATA0") (class "Default")
      (node (ref "IC1") (pin "L26") (pinfunction "PS_MIO56_L26") (pintype "bidirectional"))
    )
    (net (code "86") (name "/USB_DATA1") (class "Default")
      (node (ref "IC1") (pin "H25") (pinfunction "PS_MIO57_H25") (pintype "bidirectional"))
    )
    (net (code "87") (name "/USB_DATA2") (class "Default")
      (node (ref "IC1") (pin "M26") (pinfunction "PS_MIO54_M26") (pintype "bidirectional"))
    )
    (net (code "88") (name "/USB_DATA3") (class "Default")
      (node (ref "IC1") (pin "H27") (pinfunction "PS_MIO59_H27") (pintype "bidirectional"))
    )
    (net (code "89") (name "/USB_DATA4") (class "Default")
      (node (ref "IC1") (pin "J26") (pinfunction "PS_MIO60_J26") (pintype "bidirectional"))
    )
    (net (code "90") (name "/USB_DATA5") (class "Default")
      (node (ref "IC1") (pin "G28") (pinfunction "PS_MIO61_G28") (pintype "bidirectional"))
    )
    (net (code "91") (name "/USB_DATA6") (class "Default")
      (node (ref "IC1") (pin "K26") (pinfunction "PS_MIO62_K26") (pintype "bidirectional"))
    )
    (net (code "92") (name "/USB_DATA7") (class "Default")
      (node (ref "IC1") (pin "G29") (pinfunction "PS_MIO63_G29") (pintype "bidirectional"))
    )
    (net (code "93") (name "/USB_DIR") (class "Default")
      (node (ref "IC1") (pin "L25") (pinfunction "PS_MIO53_L25") (pintype "bidirectional"))
    )
    (net (code "94") (name "/USB_NXT") (class "Default")
      (node (ref "IC1") (pin "J25") (pinfunction "PS_MIO55_J25") (pintype "bidirectional"))
    )
    (net (code "95") (name "/USB_STP") (class "Default")
      (node (ref "IC1") (pin "H26") (pinfunction "PS_MIO58_H26") (pintype "bidirectional"))
    )
    (net (code "101") (name "GND") (class "Default")
      (node (ref "C1") (pin "1") (pinfunction "1_1") (pintype "passive"))
      (node (ref "C2") (pin "1") (pinfunction "1_1") (pintype "passive"))
      (node (ref "C3") (pin "1") (pinfunction "1_1") (pintype "passive"))
      (node (ref "C301") (pin "1") (pinfunction "1_1") (pintype "passive"))
      (node (ref "C327") (pin "1") (pinfunction "1_1") (pintype "passive"))
      (node (ref "C328") (pin "1") (pinfunction "1_1") (pintype "passive"))
      (node (ref "C329") (pin "1") (pinfunction "1_1") (pintype "passive"))
      (node (ref "C370") (pin "1") (pinfunction "1_1") (pintype "passive"))
      (node (ref "C453") (pin "1") (pinfunction "1_1") (pintype "passive"))
      (node (ref "C920") (pin "1") (pinfunction "1_1") (pintype "passive"))
      (node (ref "C956") (pin "1") (pinfunction "1_1") (pintype "passive"))
      (node (ref "C957") (pin "1") (pinfunction "1_1") (pintype "passive"))
      (node (ref "C958") (pin "1") (pinfunction "1_1") (pintype "passive"))
      (node (ref "IC3") (pin "2") (pinfunction "GND_2") (pintype "power_in"))
      (node (ref "IC37") (pin "10") (pinfunction "VSS_10") (pintype "passive"))
      (node (ref "IC40") (pin "10") (pinfunction "VSS_10") (pintype "passive"))
      (node (ref "IC41") (pin "8") (pinfunction "GND_8") (pintype "power_in"))
      (node (ref "IC42") (pin "8") (pinfunction "GND_8") (pintype "power_in"))
      (node (ref "IC53") (pin "15") (pinfunction "~{OE}_15") (pintype "input"))
      (node (ref "IC53") (pin "8") (pinfunction "GND_8") (pintype "power_in"))
      (node (ref "IC55") (pin "6") (pinfunction "GND_6") (pintype "power_in"))
      (node (ref "IC56") (pin "3") (pinfunction "GND_3") (pintype "power_in"))
      (node (ref "IC57") (pin "6") (pinfunction "GND_6") (pintype "power_in"))
      (node (ref "R311") (pin "2") (pinfunction "2_2") (pintype "passive"))
      (node (ref "R572") (pin "1") (pinfunction "1_1") (pintype "passive"))
      (node (ref "R573") (pin "1") (pinfunction "1_1") (pintype "passive"))
      (node (ref "R574") (pin "1") (pinfunction "1_1") (pintype "passive"))
      (node (ref "T22") (pin "2") (pinfunction "S_2") (pintype "passive"))
    )
    (net (code "102") (name "Net-(IC1S-PS_MIO6)") (class "Default")
      (node (ref "IC1") (pin "W26") (pinfunction "PS_MIO6_W26") (pintype "bidirectional"))
      (node (ref "TP11") (pin "1") (pinfunction "1_1") (pintype "passive"))
    )
    (net (code "103") (name "Net-(IC1S-PS_MIO7)") (class "Default")
      (node (ref "IC1") (pin "T26") (pinfunction "PS_MIO7_T26") (pintype "bidirectional"))
      (node (ref "TP12") (pin "1") (pinfunction "1_1") (pintype "passive"))
    )
    (net (code "104") (name "Net-(IC1S-PS_MIO8)") (class "Default")
      (node (ref "IC1") (pin "U27") (pinfunction "PS_MIO8_U27") (pintype "bidirectional"))
      (node (ref "TP13") (pin "1") (pinfunction "1_1") (pintype "passive"))
    )
    (net (code "105") (name "Net-(IC1S-PS_MIO9)") (class "Default")
      (node (ref "IC1") (pin "R27") (pinfunction "PS_MIO9_R27") (pintype "bidirectional"))
      (node (ref "TP14") (pin "1") (pinfunction "1_1") (pintype "passive"))
    )
    (net (code "106") (name "Net-(IC1S-PS_MIO10)") (class "Default")
      (node (ref "IC1") (pin "V27") (pinfunction "PS_MIO10_V27") (pintype "bidirectional"))
      (node (ref "TP15") (pin "1") (pinfunction "1_1") (pintype "passive"))
    )
    (net (code "107") (name "Net-(IC1S-PS_MIO11)") (class "Default")
      (node (ref "IC1") (pin "P28") (pinfunction "PS_MIO11_P28") (pintype "bidirectional"))
      (node (ref "TP16") (pin "1") (pinfunction "1_1") (pintype "passive"))
    )
    (net (code "108") (name "Net-(IC1S-PS_MIO16)") (class "Default")
      (node (ref "IC1") (pin "R29") (pinfunction "PS_MIO16_R29") (pintype "bidirectional"))
      (node (ref "IC3") (pin "5") (pinfunction "A1_5") (pintype "bidirectional"))
      (node (ref "R569") (pin "1") (pinfunction "1_1") (pintype "passive"))
    )
    (net (code "109") (name "Net-(IC1S-PS_MIO17)") (class "Default")
      (node (ref "IC1") (pin "T29") (pinfunction "PS_MIO17_T29") (pintype "bidirectional"))
      (node (ref "IC3") (pin "4") (pinfunction "A2_4") (pintype "bidirectional"))
      (node (ref "R433") (pin "1") (pinfunction "1_1") (pintype "passive"))
    )
    (net (code "110") (name "Net-(IC1S-PS_MIO22)") (class "Default")
      (node (ref "IC1") (pin "Y28") (pinfunction "PS_MIO22_Y28") (pintype "bidirectional"))
      (node (ref "TP17") (pin "1") (pinfunction "1_1") (pintype "passive"))
    )
    (net (code "111") (name "Net-(IC1S-PS_MIO23)") (class "Default")
      (node (ref "IC1") (pin "U29") (pinfunction "PS_MIO23_U29") (pintype "bidirectional"))
      (node (ref "TP18") (pin "1") (pinfunction "1_1") (pintype "passive"))
    )
    (net (code "112") (name "Net-(IC1S-PS_MIO24)") (class "Default")
      (node (ref "IC1") (pin "Y29") (pinfunction "PS_MIO24_Y29") (pintype "bidirectional"))
      (node (ref "TP19") (pin "1") (pinfunction "1_1") (pintype "passive"))
    )
    (net (code "113") (name "Net-(IC1S-PS_MIO25)") (class "Default")
      (node (ref "IC1") (pin "W29") (pinfunction "PS_MIO25_W29") (pintype "bidirectional"))
      (node (ref "TP20") (pin "1") (pinfunction "1_1") (pintype "passive"))
    )
    (net (code "114") (name "Net-(IC1T-PS_MIO26)") (class "Default")
      (node (ref "IC1") (pin "G25") (pinfunction "PS_MIO26_G25") (pintype "bidirectional"))
      (node (ref "R165") (pin "2") (pinfunction "2_2") (pintype "passive"))
    )
    (net (code "115") (name "Net-(IC1T-PS_MIO27)") (class "Default")
      (node (ref "IC1") (pin "C25") (pinfunction "PS_MIO27_C25") (pintype "bidirectional"))
      (node (ref "R287") (pin "2") (pinfunction "2_2") (pintype "passive"))
    )
    (net (code "116") (name "Net-(IC1T-PS_MIO28)") (class "Default")
      (node (ref "IC1") (pin "F25") (pinfunction "PS_MIO28_F25") (pintype "bidirectional"))
      (node (ref "R288") (pin "2") (pinfunction "2_2") (pintype "passive"))
    )
    (net (code "117") (name "Net-(IC1T-PS_MIO29)") (class "Default")
      (node (ref "IC1") (pin "B25") (pinfunction "PS_MIO29_B25") (pintype "bidirectional"))
      (node (ref "R289") (pin "2") (pinfunction "2_2") (pintype "passive"))
    )
    (net (code "118") (name "Net-(IC1T-PS_MIO30)") (class "Default")
      (node (ref "IC1") (pin "D25") (pinfunction "PS_MIO30_D25") (pintype "bidirectional"))
      (node (ref "R290") (pin "2") (pinfunction "2_2") (pintype "passive"))
    )
    (net (code "119") (name "Net-(IC1T-PS_MIO31)") (class "Default")
      (node (ref "IC1") (pin "C26") (pinfunction "PS_MIO31_C26") (pintype "bidirectional"))
      (node (ref "R291") (pin "2") (pinfunction "2_2") (pintype "passive"))
    )
    (net (code "120") (name "Net-(IC1T-PS_MIO38)") (class "Default")
      (node (ref "IC1") (pin "E27") (pinfunction "PS_MIO38_E27") (pintype "bidirectional"))
      (node (ref "TP21") (pin "1") (pinfunction "1_1") (pintype "passive"))
    )
    (net (code "121") (name "Net-(IC1T-PS_MIO43)") (class "Default")
      (node (ref "IC1") (pin "D28") (pinfunction "PS_MIO43_D28") (pintype "bidirectional"))
      (node (ref "TP24") (pin "1") (pinfunction "1_1") (pintype "passive"))
    )
    (net (code "122") (name "Net-(IC1U-PS_MIO64)") (class "Default")
      (node (ref "IC1") (pin "K27") (pinfunction "PS_MIO64_K27") (pintype "bidirectional"))
      (node (ref "R305") (pin "2") (pinfunction "2_2") (pintype "passive"))
    )
    (net (code "123") (name "Net-(IC1U-PS_MIO65)") (class "Default")
      (node (ref "IC1") (pin "L27") (pinfunction "PS_MIO65_L27") (pintype "bidirectional"))
      (node (ref "R306") (pin "2") (pinfunction "2_2") (pintype "passive"))
    )
    (net (code "124") (name "Net-(IC1U-PS_MIO66)") (class "Default")
      (node (ref "IC1") (pin "N27") (pinfunction "PS_MIO66_N27") (pintype "bidirectional"))
      (node (ref "R307") (pin "2") (pinfunction "2_2") (pintype "passive"))
    )
    (net (code "125") (name "Net-(IC1U-PS_MIO67)") (class "Default")
      (node (ref "IC1") (pin "J28") (pinfunction "PS_MIO67_J28") (pintype "bidirectional"))
      (node (ref "R309") (pin "2") (pinfunction "2_2") (pintype "passive"))
    )
    (net (code "126") (name "Net-(IC1U-PS_MIO68)") (class "Default")
      (node (ref "IC1") (pin "H29") (pinfunction "PS_MIO68_H29") (pintype "bidirectional"))
      (node (ref "R310") (pin "2") (pinfunction "2_2") (pintype "passive"))
    )
    (net (code "127") (name "Net-(IC1U-PS_MIO69)") (class "Default")
      (node (ref "IC1") (pin "M27") (pinfunction "PS_MIO69_M27") (pintype "bidirectional"))
      (node (ref "R312") (pin "2") (pinfunction "2_2") (pintype "passive"))
    )
    (net (code "128") (name "Net-(IC3-OE)") (class "Default")
      (node (ref "IC3") (pin "6") (pinfunction "OE_6") (pintype "input"))
      (node (ref "R577") (pin "1") (pinfunction "1_1") (pintype "passive"))
    )
    (net (code "129") (name "Net-(IC41-~{OE})") (class "Default")
      (node (ref "IC41") (pin "15") (pinfunction "~{OE}_15") (pintype "input"))
      (node (ref "IC42") (pin "15") (pinfunction "~{OE}_15") (pintype "input"))
      (node (ref "R575") (pin "1") (pinfunction "1_1") (pintype "passive"))
      (node (ref "T22") (pin "3") (pinfunction "D_3") (pintype "passive"))
    )
    (net (code "130") (name "Net-(IC53-1A)") (class "Default")
      (node (ref "IC53") (pin "4") (pinfunction "1A_4") (pintype "output"))
      (node (ref "IC55") (pin "2") (pinfunction "A1_2") (pintype "bidirectional"))
    )
    (net (code "131") (name "Net-(IC53-2A)") (class "Default")
      (node (ref "IC53") (pin "7") (pinfunction "2A_7") (pintype "output"))
      (node (ref "IC55") (pin "3") (pinfunction "A2_3") (pintype "bidirectional"))
    )
    (net (code "132") (name "Net-(IC53-3A)") (class "Default")
      (node (ref "IC53") (pin "9") (pinfunction "3A_9") (pintype "output"))
      (node (ref "IC55") (pin "4") (pinfunction "A3_4") (pintype "bidirectional"))
    )
    (net (code "133") (name "Net-(IC53-4A)") (class "Default")
      (node (ref "IC53") (pin "12") (pinfunction "4A_12") (pintype "output"))
      (node (ref "IC55") (pin "5") (pinfunction "A4_5") (pintype "bidirectional"))
    )
    (net (code "134") (name "Net-(IC53-S)") (class "Default")
      (node (ref "IC53") (pin "1") (pinfunction "S_1") (pintype "input"))
      (node (ref "R9") (pin "1") (pinfunction "1_1") (pintype "passive"))
    )
    (net (code "135") (name "Net-(IC56-Y)") (class "Default")
      (node (ref "IC56") (pin "4") (pinfunction "Y_4") (pintype "output"))
      (node (ref "R308") (pin "2") (pinfunction "2_2") (pintype "passive"))
    )
    (net (code "136") (name "Net-(T22-G)") (class "Default")
      (node (ref "R574") (pin "2") (pinfunction "2_2") (pintype "passive"))
      (node (ref "R576") (pin "2") (pinfunction "2_2") (pintype "passive"))
      (node (ref "T22") (pin "1") (pinfunction "G_1") (pintype "passive"))
    )
    (net (code "137") (name "P1V8") (class "Default")
      (node (ref "C3") (pin "2") (pinfunction "2_2") (pintype "passive"))
      (node (ref "C301") (pin "2") (pinfunction "2_2") (pintype "passive"))
      (node (ref "C327") (pin "2") (pinfunction "2_2") (pintype "passive"))
      (node (ref "C370") (pin "2") (pinfunction "2_2") (pintype "passive"))
      (node (ref "C920") (pin "2") (pinfunction "2_2") (pintype "passive"))
      (node (ref "C957") (pin "2") (pinfunction "2_2") (pintype "passive"))
      (node (ref "IC3") (pin "3") (pinfunction "Vcca_3") (pintype "power_in"))
      (node (ref "IC37") (pin "2") (pinfunction "VCC_2") (pintype "passive"))
      (node (ref "IC40") (pin "2") (pinfunction "VCC_2") (pintype "passive"))
      (node (ref "IC55") (pin "1") (pinfunction "VCCA_1") (pintype "power_in"))
      (node (ref "IC55") (pin "12") (pinfunction "OE_12") (pintype "input"))
      (node (ref "IC57") (pin "1") (pinfunction "VCCA_1") (pintype "power_in"))
      (node (ref "IC57") (pin "12") (pinfunction "OE_12") (pintype "input"))
      (node (ref "R10") (pin "2") (pinfunction "2_2") (pintype "passive"))
      (node (ref "R11") (pin "1") (pinfunction "1_1") (pintype "passive"))
      (node (ref "R12") (pin "2") (pinfunction "2_2") (pintype "passive"))
      (node (ref "R433") (pin "2") (pinfunction "2_2") (pintype "passive"))
      (node (ref "R553") (pin "2") (pinfunction "2_2") (pintype "passive"))
      (node (ref "R569") (pin "2") (pinfunction "2_2") (pintype "passive"))
      (node (ref "R570") (pin "1") (pinfunction "1_1") (pintype "passive"))
      (node (ref "R571") (pin "2") (pinfunction "2_2") (pintype "passive"))
      (node (ref "R577") (pin "2") (pinfunction "2_2") (pintype "passive"))
    )
    (net (code "138") (name "P3V3") (class "Default")
      (node (ref "C328") (pin "2") (pinfunction "2_2") (pintype "passive"))
      (node (ref "C329") (pin "2") (pinfunction "2_2") (pintype "passive"))
      (node (ref "IC41") (pin "16") (pinfunction "VCC_16") (pintype "power_in"))
      (node (ref "IC42") (pin "16") (pinfunction "VCC_16") (pintype "power_in"))
      (node (ref "IC53") (pin "16") (pinfunction "VCC_16") (pintype "power_in"))
      (node (ref "IC56") (pin "5") (pinfunction "VCC_5") (pintype "power_in"))
      (node (ref "R575") (pin "2") (pinfunction "2_2") (pintype "passive"))
    )
    (net (code "139") (name "P3V3MP") (class "Default")
      (node (ref "C1") (pin "2") (pinfunction "2_2") (pintype "passive"))
      (node (ref "C2") (pin "2") (pinfunction "2_2") (pintype "passive"))
      (node (ref "C453") (pin "2") (pinfunction "2_2") (pintype "passive"))
      (node (ref "C956") (pin "2") (pinfunction "2_2") (pintype "passive"))
      (node (ref "C958") (pin "2") (pinfunction "2_2") (pintype "passive"))
      (node (ref "IC3") (pin "7") (pinfunction "Vccb_7") (pintype "power_in"))
      (node (ref "IC55") (pin "11") (pinfunction "VCCB_11") (pintype "power_in"))
      (node (ref "IC57") (pin "11") (pinfunction "VCCB_11") (pintype "power_in"))
      (node (ref "R576") (pin "1") (pinfunction "1_1") (pintype "passive"))
    )
    (net (code "140") (name "unconnected-(IC1S-PS_MIO12-PadN29)") (class "Default")
      (node (ref "IC1") (pin "N29") (pinfunction "PS_MIO12_N29") (pintype "bidirectional"))
    )
    (net (code "141") (name "unconnected-(IC1S-PS_MIO13-PadR28)") (class "Default")
      (node (ref "IC1") (pin "R28") (pinfunction "PS_MIO13_R28") (pintype "bidirectional"))
    )
    (net (code "142") (name "unconnected-(IC1S-PS_MIO14-PadP29)") (class "Default")
      (node (ref "IC1") (pin "P29") (pinfunction "PS_MIO14_P29") (pintype "bidirectional"))
    )
    (net (code "143") (name "unconnected-(IC1S-PS_MIO15-PadU28)") (class "Default")
      (node (ref "IC1") (pin "U28") (pinfunction "PS_MIO15_U28") (pintype "bidirectional"))
    )
    (net (code "144") (name "unconnected-(IC37-DNU0-Pad3)") (class "Default")
      (node (ref "IC37") (pin "3") (pinfunction "DNU0_3") (pintype "passive"))
    )
    (net (code "145") (name "unconnected-(IC37-DNU1-Pad4)") (class "Default")
      (node (ref "IC37") (pin "4") (pinfunction "DNU1_4") (pintype "passive"))
    )
    (net (code "146") (name "unconnected-(IC37-DNU2-Pad5)") (class "Default")
      (node (ref "IC37") (pin "5") (pinfunction "DNU2_5") (pintype "passive"))
    )
    (net (code "147") (name "unconnected-(IC37-DNU3-Pad6)") (class "Default")
      (node (ref "IC37") (pin "6") (pinfunction "DNU3_6") (pintype "passive"))
    )
    (net (code "148") (name "unconnected-(IC37-DNU4-Pad11)") (class "Default")
      (node (ref "IC37") (pin "11") (pinfunction "DNU4_11") (pintype "passive"))
    )
    (net (code "149") (name "unconnected-(IC37-DNU5-Pad12)") (class "Default")
      (node (ref "IC37") (pin "12") (pinfunction "DNU5_12") (pintype "passive"))
    )
    (net (code "150") (name "unconnected-(IC37-DNU6-Pad13)") (class "Default")
      (node (ref "IC37") (pin "13") (pinfunction "DNU6_13") (pintype "passive"))
    )
    (net (code "151") (name "unconnected-(IC37-DNU7-Pad14)") (class "Default")
      (node (ref "IC37") (pin "14") (pinfunction "DNU7_14") (pintype "passive"))
    )
    (net (code "152") (name "unconnected-(IC40-DNU0-Pad3)") (class "Default")
      (node (ref "IC40") (pin "3") (pinfunction "DNU0_3") (pintype "passive"))
    )
    (net (code "153") (name "unconnected-(IC40-DNU1-Pad4)") (class "Default")
      (node (ref "IC40") (pin "4") (pinfunction "DNU1_4") (pintype "passive"))
    )
    (net (code "154") (name "unconnected-(IC40-DNU2-Pad5)") (class "Default")
      (node (ref "IC40") (pin "5") (pinfunction "DNU2_5") (pintype "passive"))
    )
    (net (code "155") (name "unconnected-(IC40-DNU3-Pad6)") (class "Default")
      (node (ref "IC40") (pin "6") (pinfunction "DNU3_6") (pintype "passive"))
    )
    (net (code "156") (name "unconnected-(IC40-DNU4-Pad11)") (class "Default")
      (node (ref "IC40") (pin "11") (pinfunction "DNU4_11") (pintype "passive"))
    )
    (net (code "157") (name "unconnected-(IC40-DNU5-Pad12)") (class "Default")
      (node (ref "IC40") (pin "12") (pinfunction "DNU5_12") (pintype "passive"))
    )
    (net (code "158") (name "unconnected-(IC40-DNU6-Pad13)") (class "Default")
      (node (ref "IC40") (pin "13") (pinfunction "DNU6_13") (pintype "passive"))
    )
    (net (code "159") (name "unconnected-(IC40-DNU7-Pad14)") (class "Default")
      (node (ref "IC40") (pin "14") (pinfunction "DNU7_14") (pintype "passive"))
    )
    (net (code "160") (name "unconnected-(IC41-2B2-Pad6)") (class "Default")
      (node (ref "IC41") (pin "6") (pinfunction "2B2_6") (pintype "input"))
    )
    (net (code "161") (name "unconnected-(IC42-3A-Pad9)") (class "Default")
      (node (ref "IC42") (pin "9") (pinfunction "3A_9") (pintype "output"))
    )
    (net (code "162") (name "unconnected-(IC42-3B1-Pad11)") (class "Default")
      (node (ref "IC42") (pin "11") (pinfunction "3B1_11") (pintype "input"))
    )
    (net (code "163") (name "unconnected-(IC42-3B2-Pad10)") (class "Default")
      (node (ref "IC42") (pin "10") (pinfunction "3B2_10") (pintype "input"))
    )
    (net (code "164") (name "unconnected-(IC42-4A-Pad12)") (class "Default")
      (node (ref "IC42") (pin "12") (pinfunction "4A_12") (pintype "output"))
    )
    (net (code "165") (name "unconnected-(IC42-4B1-Pad14)") (class "Default")
      (node (ref "IC42") (pin "14") (pinfunction "4B1_14") (pintype "input"))
    )
    (net (code "166") (name "unconnected-(IC42-4B2-Pad13)") (class "Default")
      (node (ref "IC42") (pin "13") (pinfunction "4B2_13") (pintype "input"))
    )
    (net (code "167") (name "unconnected-(IC57-A3-Pad4)") (class "Default")
      (node (ref "IC57") (pin "4") (pinfunction "A3_4") (pintype "bidirectional"))
    )
    (net (code "168") (name "unconnected-(IC57-A4-Pad5)") (class "Default")
      (node (ref "IC57") (pin "5") (pinfunction "A4_5") (pintype "bidirectional"))
    )
    (net (code "169") (name "unconnected-(IC57-B3-Pad8)") (class "Default")
      (node (ref "IC57") (pin "8") (pinfunction "B3_8") (pintype "bidirectional"))
    )
    (net (code "170") (name "unconnected-(IC57-B4-Pad7)") (class "Default")
      (node (ref "IC57") (pin "7") (pinfunction "B4_7") (pintype "bidirectional"))
    )
  )
)
